# P1.net
KiCad netlist of a schematic drawn in Altium Designer
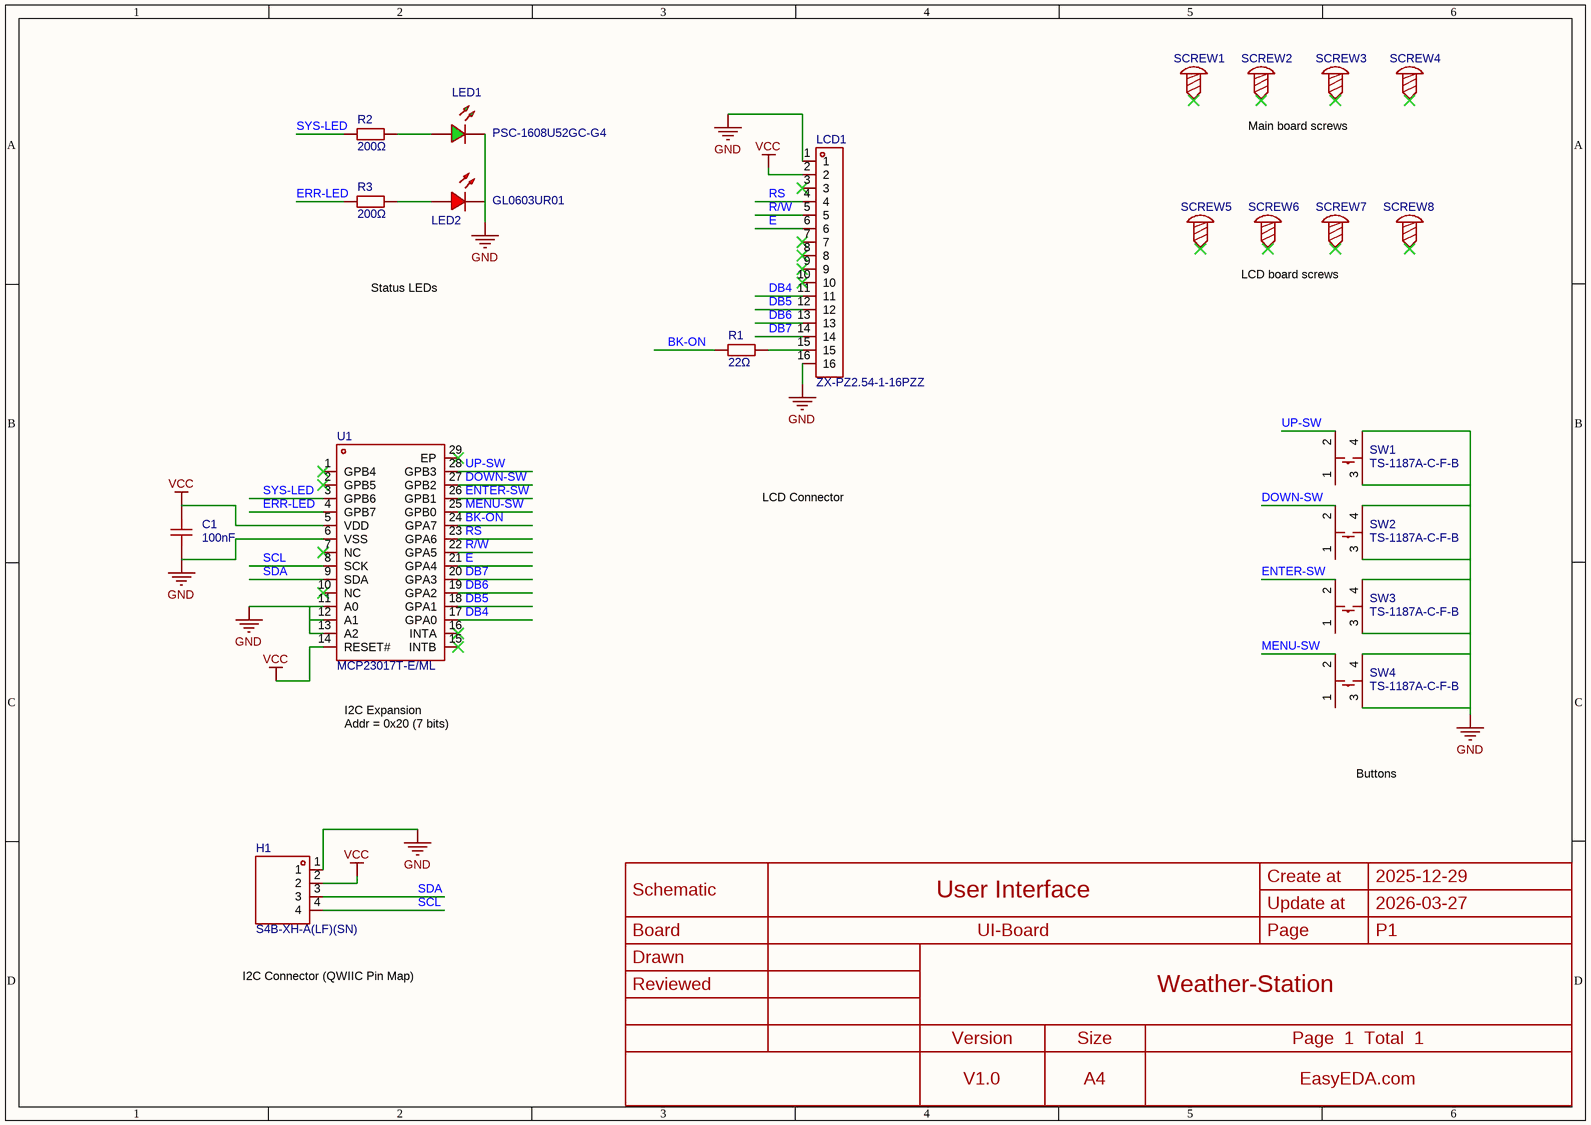
[diagram p0: P1.schdoc]

(export (version "E")
  (design (tool "Eeschema 10.0.6"))
  (components
    (comp (ref "C1")
      (value "100nF")
      (footprint "C0402")
      (description "Capacitance:100nF Tolerance:±10% Tolerance:±10% Voltage Rating:16V Temperature Coefficient:X7R")
      (fields (field (name "MANUFACTURER") "SAMSUNG(三星)") (field (name "MANUFACTURERPART") "CL05B104KO5NNNC"))
      (libsource (lib "altium-import") (part "root_1_CL05B104KO5NNNC_"))
    )
    (comp (ref "H1")
      (value "S4B-XH-A(LF)(SN)")
      (footprint "CONN-TH_S4B-XH-A-LF-SN")
      (fields (field (name "MANUFACTURER") "JST"))
      (libsource (lib "altium-import") (part "root_0_mirrored_S4B-XH-A(LF)(SN)_"))
    )
    (comp (ref "LCD1")
      (value "ZX-PZ2.54-1-16PZZ")
      (footprint "HDR-TH_16P-P2.54-V-M-2")
      (fields (field (name "MANUFACTURER") "Megastar(兆星)"))
      (libsource (lib "altium-import") (part "root_0_ZX-PZ2.54-1-16PZZ_"))
    )
    (comp (ref "LED1")
      (value "PSC-1608U52GC-G4")
      (footprint "LED0603-RD_GREEN")
      (fields (field (name "MANUFACTURER") "HONGLITRONIC(鸿利光电)"))
      (libsource (lib "altium-import") (part "root_0_PSC-1608U52GC-G4_"))
    )
    (comp (ref "LED2")
      (value "GL0603UR01")
      (footprint "LED0603-FD")
      (fields (field (name "MANUFACTURER") "Guiguang light(桂光光电)"))
      (libsource (lib "altium-import") (part "root_0_GL0603UR01_"))
    )
    (comp (ref "R1")
      (value "22Ω")
      (footprint "R0402")
      (fields
        (field (name "MANUFACTURER") "VO(翔胜)")
        (field (name "MANUFACTURERPART") "SCR0402F22R")
        (field (name "TOLERANCE") "±1%")
      )
      (libsource (lib "altium-import") (part "root_0_SCR0402F22R_"))
    )
    (comp (ref "R2")
      (value "200Ω")
      (footprint "R0402")
      (fields
        (field (name "MANUFACTURER") "GiantOhm(鼎声微电)")
        (field (name "MANUFACTURERPART") "GR0402F200RTAG00")
        (field (name "TOLERANCE") "±1%")
      )
      (libsource (lib "altium-import") (part "root_0_GR0402F200RTAG00_"))
    )
    (comp (ref "R3")
      (value "200Ω")
      (footprint "R0402")
      (fields
        (field (name "MANUFACTURER") "GiantOhm(鼎声微电)")
        (field (name "MANUFACTURERPART") "GR0402F200RTAG00")
        (field (name "TOLERANCE") "±1%")
      )
      (libsource (lib "altium-import") (part "root_0_GR0402F200RTAG00_"))
    )
    (comp (ref "SCREW1")
      (value "~")
      (footprint "Screw-Hole-M3")
      (libsource (lib "altium-import") (part "root_0_Screw-Hole-M3_"))
    )
    (comp (ref "SCREW2")
      (value "~")
      (footprint "Screw-Hole-M3")
      (libsource (lib "altium-import") (part "root_0_Screw-Hole-M3_"))
    )
    (comp (ref "SCREW3")
      (value "~")
      (footprint "Screw-Hole-M3")
      (libsource (lib "altium-import") (part "root_0_Screw-Hole-M3_"))
    )
    (comp (ref "SCREW4")
      (value "~")
      (footprint "Screw-Hole-M3")
      (libsource (lib "altium-import") (part "root_0_Screw-Hole-M3_"))
    )
    (comp (ref "SCREW5")
      (value "~")
      (footprint "Screw-Hole-M3")
      (libsource (lib "altium-import") (part "root_0_Screw-Hole-M3_"))
    )
    (comp (ref "SCREW6")
      (value "~")
      (footprint "Screw-Hole-M3")
      (libsource (lib "altium-import") (part "root_0_Screw-Hole-M3_"))
    )
    (comp (ref "SCREW7")
      (value "~")
      (footprint "Screw-Hole-M3")
      (libsource (lib "altium-import") (part "root_0_Screw-Hole-M3_"))
    )
    (comp (ref "SCREW8")
      (value "~")
      (footprint "Screw-Hole-M3")
      (libsource (lib "altium-import") (part "root_0_Screw-Hole-M3_"))
    )
    (comp (ref "SW1")
      (value "TS-1187A-C-F-B")
      (footprint "SW-SMD_4P-L5.1-W5.1-P3.70-LS6.5-TL_H3.0")
      (fields (field (name "MANUFACTURER") "XKB Connection(中国星坤)"))
      (libsource (lib "altium-import") (part "root_1_TS-1187A-C-F-B_"))
    )
    (comp (ref "SW2")
      (value "TS-1187A-C-F-B")
      (footprint "SW-SMD_4P-L5.1-W5.1-P3.70-LS6.5-TL_H3.0")
      (fields (field (name "MANUFACTURER") "XKB Connection(中国星坤)"))
      (libsource (lib "altium-import") (part "root_1_TS-1187A-C-F-B_"))
    )
    (comp (ref "SW3")
      (value "TS-1187A-C-F-B")
      (footprint "SW-SMD_4P-L5.1-W5.1-P3.70-LS6.5-TL_H3.0")
      (fields (field (name "MANUFACTURER") "XKB Connection(中国星坤)"))
      (libsource (lib "altium-import") (part "root_1_TS-1187A-C-F-B_"))
    )
    (comp (ref "SW4")
      (value "TS-1187A-C-F-B")
      (footprint "SW-SMD_4P-L5.1-W5.1-P3.70-LS6.5-TL_H3.0")
      (fields (field (name "MANUFACTURER") "XKB Connection(中国星坤)"))
      (libsource (lib "altium-import") (part "root_1_TS-1187A-C-F-B_"))
    )
    (comp (ref "U1")
      (value "MCP23017T-E/ML")
      (footprint "QFN-28_L6.0-W6.0-P0.65-BL-EP3.7")
      (fields (field (name "MANUFACTURER") "MICROCHIP(美国微芯)"))
      (libsource (lib "altium-import") (part "root_0_MCP23017T-E/ML_"))
    )
  )
  (nets
    (net (code "1") (name "/BK-ON") (class "Default")
      (node (ref "R1") (pin "1") (pinfunction "1_1") (pintype "passive"))
      (node (ref "U1") (pin "24") (pinfunction "GPA7_24") (pintype "passive"))
    )
    (net (code "2") (name "/DB4") (class "Default")
      (node (ref "LCD1") (pin "11") (pinfunction "11_11") (pintype "passive"))
      (node (ref "U1") (pin "17") (pinfunction "GPA0_17") (pintype "passive"))
    )
    (net (code "3") (name "/DB5") (class "Default")
      (node (ref "LCD1") (pin "12") (pinfunction "12_12") (pintype "passive"))
      (node (ref "U1") (pin "18") (pinfunction "GPA1_18") (pintype "passive"))
    )
    (net (code "4") (name "/DB6") (class "Default")
      (node (ref "LCD1") (pin "13") (pinfunction "13_13") (pintype "passive"))
      (node (ref "U1") (pin "19") (pinfunction "GPA2_19") (pintype "passive"))
    )
    (net (code "5") (name "/DB7") (class "Default")
      (node (ref "LCD1") (pin "14") (pinfunction "14_14") (pintype "passive"))
      (node (ref "U1") (pin "20") (pinfunction "GPA3_20") (pintype "passive"))
    )
    (net (code "6") (name "/DOWN-SW") (class "Default")
      (node (ref "SW2") (pin "2") (pinfunction "B_2") (pintype "passive"))
      (node (ref "U1") (pin "27") (pinfunction "GPB2_27") (pintype "passive"))
    )
    (net (code "7") (name "/E") (class "Default")
      (node (ref "LCD1") (pin "6") (pinfunction "6_6") (pintype "passive"))
      (node (ref "U1") (pin "21") (pinfunction "GPA4_21") (pintype "passive"))
    )
    (net (code "8") (name "/ENTER-SW") (class "Default")
      (node (ref "SW3") (pin "2") (pinfunction "B_2") (pintype "passive"))
      (node (ref "U1") (pin "26") (pinfunction "GPB1_26") (pintype "passive"))
    )
    (net (code "9") (name "/ERR-LED") (class "Default")
      (node (ref "R3") (pin "1") (pinfunction "1_1") (pintype "passive"))
      (node (ref "U1") (pin "4") (pinfunction "GPB7_4") (pintype "passive"))
    )
    (net (code "10") (name "/MENU-SW") (class "Default")
      (node (ref "SW4") (pin "2") (pinfunction "B_2") (pintype "passive"))
      (node (ref "U1") (pin "25") (pinfunction "GPB0_25") (pintype "passive"))
    )
    (net (code "11") (name "/RS") (class "Default")
      (node (ref "LCD1") (pin "4") (pinfunction "4_4") (pintype "passive"))
      (node (ref "U1") (pin "23") (pinfunction "GPA6_23") (pintype "passive"))
    )
    (net (code "12") (name "/R{slash}W") (class "Default")
      (node (ref "LCD1") (pin "5") (pinfunction "5_5") (pintype "passive"))
      (node (ref "U1") (pin "22") (pinfunction "GPA5_22") (pintype "passive"))
    )
    (net (code "13") (name "/SCL") (class "Default")
      (node (ref "H1") (pin "4") (pinfunction "4_4") (pintype "passive"))
      (node (ref "U1") (pin "8") (pinfunction "SCK_8") (pintype "passive"))
    )
    (net (code "14") (name "/SDA") (class "Default")
      (node (ref "H1") (pin "3") (pinfunction "3_3") (pintype "passive"))
      (node (ref "U1") (pin "9") (pinfunction "SDA_9") (pintype "passive"))
    )
    (net (code "15") (name "/SYS-LED") (class "Default")
      (node (ref "R2") (pin "1") (pinfunction "1_1") (pintype "passive"))
      (node (ref "U1") (pin "3") (pinfunction "GPB6_3") (pintype "passive"))
    )
    (net (code "16") (name "/UP-SW") (class "Default")
      (node (ref "SW1") (pin "2") (pinfunction "B_2") (pintype "passive"))
      (node (ref "U1") (pin "28") (pinfunction "GPB3_28") (pintype "passive"))
    )
    (net (code "17") (name "GND") (class "Default")
      (node (ref "C1") (pin "2") (pinfunction "2_2") (pintype "passive"))
      (node (ref "H1") (pin "1") (pinfunction "1_1") (pintype "passive"))
      (node (ref "LCD1") (pin "1") (pinfunction "1_1") (pintype "passive"))
      (node (ref "LCD1") (pin "16") (pinfunction "16_16") (pintype "passive"))
      (node (ref "LED1") (pin "1") (pinfunction "C_1") (pintype "passive"))
      (node (ref "LED2") (pin "2") (pinfunction "C_2") (pintype "passive"))
      (node (ref "SW1") (pin "3") (pinfunction "C_3") (pintype "passive"))
      (node (ref "SW1") (pin "4") (pinfunction "D_4") (pintype "passive"))
      (node (ref "SW2") (pin "3") (pinfunction "C_3") (pintype "passive"))
      (node (ref "SW2") (pin "4") (pinfunction "D_4") (pintype "passive"))
      (node (ref "SW3") (pin "3") (pinfunction "C_3") (pintype "passive"))
      (node (ref "SW3") (pin "4") (pinfunction "D_4") (pintype "passive"))
      (node (ref "SW4") (pin "3") (pinfunction "C_3") (pintype "passive"))
      (node (ref "SW4") (pin "4") (pinfunction "D_4") (pintype "passive"))
      (node (ref "U1") (pin "11") (pinfunction "A0_11") (pintype "passive"))
      (node (ref "U1") (pin "12") (pinfunction "A1_12") (pintype "passive"))
      (node (ref "U1") (pin "13") (pinfunction "A2_13") (pintype "passive"))
      (node (ref "U1") (pin "6") (pinfunction "VSS_6") (pintype "passive"))
    )
    (net (code "18") (name "Net-(LCD1-Pad15)") (class "Default")
      (node (ref "LCD1") (pin "15") (pinfunction "15_15") (pintype "passive"))
      (node (ref "R1") (pin "2") (pinfunction "2_2") (pintype "passive"))
    )
    (net (code "19") (name "Net-(LED1-A)") (class "Default")
      (node (ref "LED1") (pin "2") (pinfunction "A_2") (pintype "passive"))
      (node (ref "R2") (pin "2") (pinfunction "2_2") (pintype "passive"))
    )
    (net (code "20") (name "Net-(LED2-A)") (class "Default")
      (node (ref "LED2") (pin "1") (pinfunction "A_1") (pintype "passive"))
      (node (ref "R3") (pin "2") (pinfunction "2_2") (pintype "passive"))
    )
    (net (code "21") (name "VCC") (class "Default")
      (node (ref "C1") (pin "1") (pinfunction "1_1") (pintype "passive"))
      (node (ref "H1") (pin "2") (pinfunction "2_2") (pintype "passive"))
      (node (ref "LCD1") (pin "2") (pinfunction "2_2") (pintype "passive"))
      (node (ref "U1") (pin "14") (pinfunction "RESET#_14") (pintype "passive"))
      (node (ref "U1") (pin "5") (pinfunction "VDD_5") (pintype "passive"))
    )
    (net (code "22") (name "unconnected-(LCD1-Pad3)") (class "Default")
      (node (ref "LCD1") (pin "3") (pinfunction "3_3") (pintype "passive+no_connect"))
    )
    (net (code "23") (name "unconnected-(LCD1-Pad7)") (class "Default")
      (node (ref "LCD1") (pin "7") (pinfunction "7_7") (pintype "passive+no_connect"))
    )
    (net (code "24") (name "unconnected-(LCD1-Pad8)") (class "Default")
      (node (ref "LCD1") (pin "8") (pinfunction "8_8") (pintype "passive+no_connect"))
    )
    (net (code "25") (name "unconnected-(LCD1-Pad9)") (class "Default")
      (node (ref "LCD1") (pin "9") (pinfunction "9_9") (pintype "passive+no_connect"))
    )
    (net (code "26") (name "unconnected-(LCD1-Pad10)") (class "Default")
      (node (ref "LCD1") (pin "10") (pinfunction "10_10") (pintype "passive+no_connect"))
    )
    (net (code "27") (name "unconnected-(SCREW1-Pad1)") (class "Default")
      (node (ref "SCREW1") (pin "1") (pinfunction "1_1") (pintype "passive+no_connect"))
    )
    (net (code "28") (name "unconnected-(SCREW2-Pad1)") (class "Default")
      (node (ref "SCREW2") (pin "1") (pinfunction "1_1") (pintype "passive+no_connect"))
    )
    (net (code "29") (name "unconnected-(SCREW3-Pad1)") (class "Default")
      (node (ref "SCREW3") (pin "1") (pinfunction "1_1") (pintype "passive+no_connect"))
    )
    (net (code "30") (name "unconnected-(SCREW4-Pad1)") (class "Default")
      (node (ref "SCREW4") (pin "1") (pinfunction "1_1") (pintype "passive+no_connect"))
    )
    (net (code "31") (name "unconnected-(SCREW5-Pad1)") (class "Default")
      (node (ref "SCREW5") (pin "1") (pinfunction "1_1") (pintype "passive+no_connect"))
    )
    (net (code "32") (name "unconnected-(SCREW6-Pad1)") (class "Default")
      (node (ref "SCREW6") (pin "1") (pinfunction "1_1") (pintype "passive+no_connect"))
    )
    (net (code "33") (name "unconnected-(SCREW7-Pad1)") (class "Default")
      (node (ref "SCREW7") (pin "1") (pinfunction "1_1") (pintype "passive+no_connect"))
    )
    (net (code "34") (name "unconnected-(SCREW8-Pad1)") (class "Default")
      (node (ref "SCREW8") (pin "1") (pinfunction "1_1") (pintype "passive+no_connect"))
    )
    (net (code "35") (name "unconnected-(SW1-A-Pad1)") (class "Default")
      (node (ref "SW1") (pin "1") (pinfunction "A_1") (pintype "passive"))
    )
    (net (code "36") (name "unconnected-(SW2-A-Pad1)") (class "Default")
      (node (ref "SW2") (pin "1") (pinfunction "A_1") (pintype "passive"))
    )
    (net (code "37") (name "unconnected-(SW3-A-Pad1)") (class "Default")
      (node (ref "SW3") (pin "1") (pinfunction "A_1") (pintype "passive"))
    )
    (net (code "38") (name "unconnected-(SW4-A-Pad1)") (class "Default")
      (node (ref "SW4") (pin "1") (pinfunction "A_1") (pintype "passive"))
    )
    (net (code "39") (name "unconnected-(U1-EP-Pad29)") (class "Default")
      (node (ref "U1") (pin "29") (pinfunction "EP_29") (pintype "passive+no_connect"))
    )
    (net (code "40") (name "unconnected-(U1-GPB4-Pad1)") (class "Default")
      (node (ref "U1") (pin "1") (pinfunction "GPB4_1") (pintype "passive+no_connect"))
    )
    (net (code "41") (name "unconnected-(U1-GPB5-Pad2)") (class "Default")
      (node (ref "U1") (pin "2") (pinfunction "GPB5_2") (pintype "passive+no_connect"))
    )
    (net (code "42") (name "unconnected-(U1-INTA-Pad16)") (class "Default")
      (node (ref "U1") (pin "16") (pinfunction "INTA_16") (pintype "passive+no_connect"))
    )
    (net (code "43") (name "unconnected-(U1-INTB-Pad15)") (class "Default")
      (node (ref "U1") (pin "15") (pinfunction "INTB_15") (pintype "passive+no_connect"))
    )
    (net (code "44") (name "unconnected-(U1-NC-Pad7)") (class "Default")
      (node (ref "U1") (pin "7") (pinfunction "NC_7") (pintype "passive+no_connect"))
    )
    (net (code "45") (name "unconnected-(U1-NC-Pad10)") (class "Default")
      (node (ref "U1") (pin "10") (pinfunction "NC_10") (pintype "passive+no_connect"))
    )
  )
)
